# Supply.net
KiCad netlist of a schematic drawn in Altium Designer
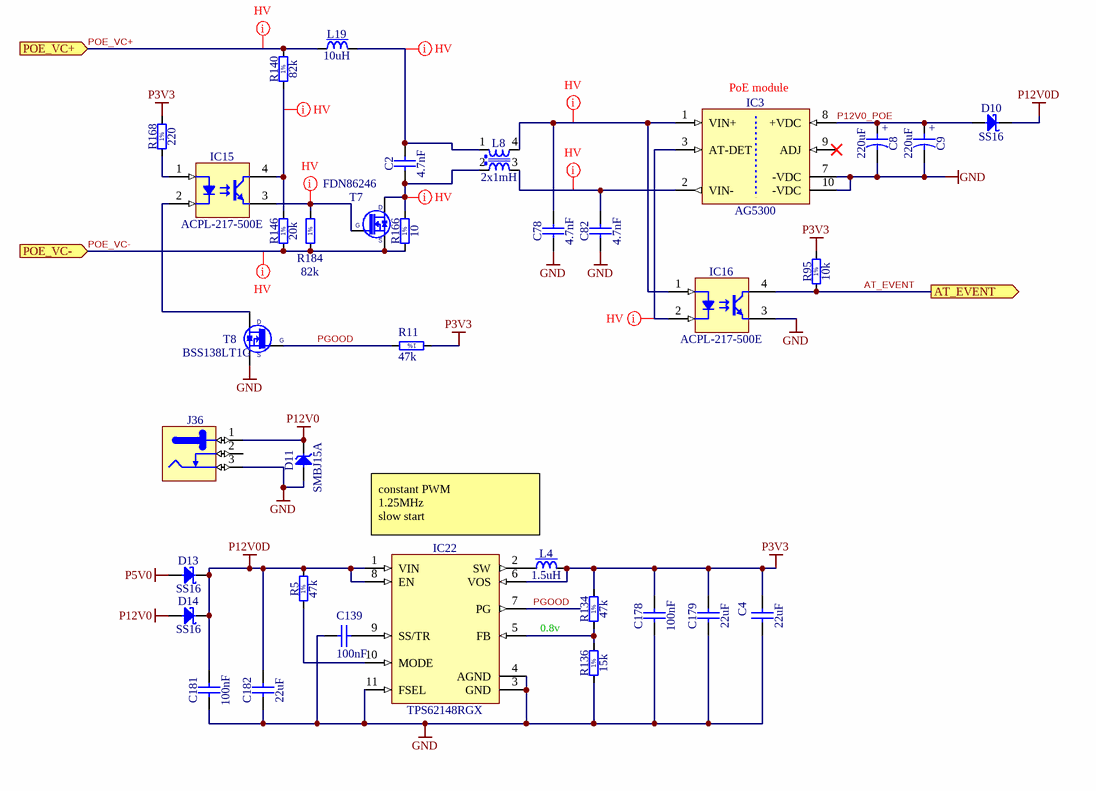
[diagram p0: Supply.SchDoc]

(export (version "E")
  (design (tool "Eeschema 10.0.6"))
  (components
    (comp (ref "C2")
      (value "4.7nF")
      (footprint "CAPC3216X140N")
      (description "Non-polarised capacitor")
      (fields
        (field (name "PART NUMBER") "CC1206_4.7NF_500V_10%_X7R")
        (field (name "VOLTAGE") "500V")
        (field (name "AUTHOR") "GK")
      )
      (libsource (lib "LIBRARY_SCH") (part "CAP_SMD_1206_4.7n_500V"))
    )
    (comp (ref "C4")
      (value "22uF")
      (footprint "CAPC2012X135N")
      (description "Non-polarised capacitor")
      (fields
        (field (name "PART NUMBER") "CC0805_22UF_16V_10%_X5R")
        (field (name "VOLTAGE") "16V")
        (field (name "AUTHOR") "CERN DEM JLC")
      )
      (libsource (lib "Capacitors") (part "Capacitor - non polarized"))
    )
    (comp (ref "C8")
      (value "220uF")
      (footprint "CAPMP7343X430N")
      (description "Polarised capacitor")
      (fields
        (field (name "PART NUMBER") "CTE7343-43_220UF_16V_10%")
        (field (name "VOLTAGE") "16V")
        (field (name "AUTHOR") "CERN DEM JLC")
      )
      (libsource (lib "Capacitors") (part "Capacitor - polarized"))
    )
    (comp (ref "C9")
      (value "220uF")
      (footprint "CAPMP7343X430N")
      (description "Polarised capacitor")
      (fields
        (field (name "PART NUMBER") "CTE7343-43_220UF_16V_10%")
        (field (name "VOLTAGE") "16V")
        (field (name "AUTHOR") "CERN DEM JLC")
      )
      (libsource (lib "Capacitors") (part "Capacitor - polarized"))
    )
    (comp (ref "C78")
      (value "4.7nF")
      (footprint "CAPC3216X140N")
      (description "Non-polarised capacitor")
      (fields
        (field (name "PART NUMBER") "CC1206_4.7NF_500V_10%_X7R")
        (field (name "VOLTAGE") "500V")
        (field (name "AUTHOR") "GK")
      )
      (libsource (lib "LIBRARY_SCH") (part "CAP_SMD_1206_4.7n_500V"))
    )
    (comp (ref "C82")
      (value "4.7nF")
      (footprint "CAPC3216X140N")
      (description "Non-polarised capacitor")
      (fields
        (field (name "PART NUMBER") "CC1206_4.7NF_500V_10%_X7R")
        (field (name "VOLTAGE") "500V")
        (field (name "AUTHOR") "GK")
      )
      (libsource (lib "LIBRARY_SCH") (part "CAP_SMD_1206_4.7n_500V"))
    )
    (comp (ref "C139")
      (value "100nF")
      (footprint "CAPC1005X55N")
      (description "Non-polarised capacitor")
      (fields
        (field (name "PART NUMBER") "CC0402_100NF_16V_10%_X5R")
        (field (name "VOLTAGE") "16V")
        (field (name "AUTHOR") "CERN DEM JLC")
      )
      (libsource (lib "Capacitors") (part "Capacitor - non polarized"))
    )
    (comp (ref "C178")
      (value "100nF")
      (footprint "CAPC1005X55N")
      (description "Non-polarised capacitor")
      (fields
        (field (name "PART NUMBER") "CC0402_100NF_16V_10%_X5R")
        (field (name "VOLTAGE") "16V")
        (field (name "AUTHOR") "CERN DEM JLC")
      )
      (libsource (lib "Capacitors") (part "Capacitor - non polarized"))
    )
    (comp (ref "C179")
      (value "22uF")
      (footprint "CAPC2012X135N")
      (description "Non-polarised capacitor")
      (fields
        (field (name "PART NUMBER") "CC0805_22UF_16V_10%_X5R")
        (field (name "VOLTAGE") "16V")
        (field (name "AUTHOR") "CERN DEM JLC")
      )
      (libsource (lib "Capacitors") (part "Capacitor - non polarized"))
    )
    (comp (ref "C181")
      (value "100nF")
      (footprint "CAPC1005X55N")
      (description "Non-polarised capacitor")
      (fields
        (field (name "PART NUMBER") "CC0402_100NF_16V_10%_X5R")
        (field (name "VOLTAGE") "16V")
        (field (name "AUTHOR") "CERN DEM JLC")
      )
      (libsource (lib "Capacitors") (part "Capacitor - non polarized"))
    )
    (comp (ref "C182")
      (value "22uF")
      (footprint "CAPC2012X135N")
      (description "Non-polarised capacitor")
      (fields
        (field (name "PART NUMBER") "CC0805_22UF_16V_10%_X5R")
        (field (name "VOLTAGE") "16V")
        (field (name "AUTHOR") "CERN DEM JLC")
      )
      (libsource (lib "Capacitors") (part "Capacitor - non polarized"))
    )
    (comp (ref "D10")
      (value "SS16")
      (footprint "DIOM5127X229N")
      (description "Schottky Diode")
      (fields
        (field (name "VOLTAGE") "60V")
        (field (name "POWER") "1A")
        (field (name "AUTHOR") "CERN DEM JLC")
      )
      (libsource (lib "ICs And Semiconductors") (part "Diode Schottky"))
    )
    (comp (ref "D11")
      (value "SMBJ15A")
      (footprint "DIOM5336X265N")
      (description "Zener Diode")
      (fields
        (field (name "VOLTAGE") "15V")
        (field (name "POWER") "600W")
        (field (name "AUTHOR") "CERN DEM JLC")
      )
      (libsource (lib "ICs And Semiconductors") (part "Diode Zener"))
    )
    (comp (ref "D13")
      (value "SS16")
      (footprint "DIOM5127X229N")
      (description "Schottky Diode")
      (fields
        (field (name "VOLTAGE") "60V")
        (field (name "POWER") "1A")
        (field (name "AUTHOR") "CERN DEM JLC")
      )
      (libsource (lib "ICs And Semiconductors") (part "Diode Schottky"))
    )
    (comp (ref "D14")
      (value "SS16")
      (footprint "DIOM5127X229N")
      (description "Schottky Diode")
      (fields
        (field (name "VOLTAGE") "60V")
        (field (name "POWER") "1A")
        (field (name "AUTHOR") "CERN DEM JLC")
      )
      (libsource (lib "ICs And Semiconductors") (part "Diode Schottky"))
    )
    (comp (ref "IC3")
      (value "AG5300")
      (footprint "SILVERTEL_AG5300")
      (description "Power-over-Ethernet Plus (POE+) Module")
      (fields (field (name "MANUFACTURER") "SILVERTEL") (field (name "AUTHOR") "CERN DEM JLC"))
      (libsource (lib "ICs And Semiconductors") (part "AG5300"))
    )
    (comp (ref "IC15")
      (value "ACPL-217-500E")
      (footprint "SOIC127P700X242-4N")
      (description "Single Optocoupler")
      (fields (field (name "MANUFACTURER") "AVAGO TECHNOLOGIES") (field (name "AUTHOR") "CERN DEM JLC"))
      (libsource (lib "ICs And Semiconductors") (part "Optocoupler Type7"))
    )
    (comp (ref "IC16")
      (value "ACPL-217-500E")
      (footprint "SOIC127P700X242-4N")
      (description "Single Optocoupler")
      (fields (field (name "MANUFACTURER") "AVAGO TECHNOLOGIES") (field (name "AUTHOR") "CERN DEM JLC"))
      (libsource (lib "ICs And Semiconductors") (part "Optocoupler Type7"))
    )
    (comp (ref "IC22")
      (value "TPS62148RGX")
      (footprint "TEXAS_RGX0011A")
      (description "3V-17V 2A Step-Down Converter, High Accuracy, With DCS-Control")
      (fields (field (name "MANUFACTURER") "TEXAS INSTRUMENTS") (field (name "AUTHOR") "CERN DEM MR"))
      (libsource (lib "ICs And Semiconductors") (part "TPS62148"))
    )
    (comp (ref "J36")
      (value "Jack")
      (footprint "CLIFF_FC68148(DC-10A)")
      (description "12V /  5A, 2.1mm Diameter Pin, DC Power Socket With  Switch. DC10A Type")
      (fields
        (field (name "PART NUMBER") "CLIFF_FC68148(DC-10A)")
        (field (name "MANUFACTURER") "CLIFF ELECTRONIC COMPONENTS")
        (field (name "AUTHOR") "CERN DEM JLC")
      )
      (libsource (lib "Connectors") (part "CLIFF_FC68148(DC-10A)"))
    )
    (comp (ref "L4")
      (value "1.5uH")
      (footprint "IND_TDK_SPM6530")
      (description "Inductor With Core")
      (fields
        (field (name "PART NUMBER") "IND_1.5UH_20%_TDK_SPM6530")
        (field (name "POWER") "11A")
        (field (name "AUTHOR") "CERN DEM MR")
      )
      (libsource (lib "Inductors & Transformers") (part "Inductor With Magnetic core"))
    )
    (comp (ref "L8")
      (value "2x1mH")
      (footprint "IND_WURTH_WE-SL2")
      (description "Inductor Common Mode")
      (fields
        (field (name "PART NUMBER") "IND_1MH_50%_WURTH_WE-SL2-744222")
        (field (name "POWER") "800mA")
        (field (name "AUTHOR") "CERN DEM JLC")
      )
      (libsource (lib "Inductors & Transformers") (part "Inductor Common Mode 1Dot-4 2Dot-3"))
    )
    (comp (ref "L19")
      (value "10uH")
      (footprint "IND_MURATA-PS_8400")
      (description "Inductor With Core")
      (fields
        (field (name "PART NUMBER") "IND_10UH_10%_MURATA-PS_8400")
        (field (name "POWER") "950mA")
        (field (name "AUTHOR") "CERN DEM JLC")
      )
      (libsource (lib "Inductors & Transformers") (part "Inductor With Magnetic core"))
    )
    (comp (ref "R5")
      (value "47k")
      (footprint "RESC1608X55N")
      (description "Resistor - 1%")
      (fields
        (field (name "PART NUMBER") "R0603_47K_1%_0.1W_100PPM")
        (field (name "POWER") "0.1W")
        (field (name "AUTHOR") "CERN DEM JLC")
      )
      (libsource (lib "Resistors") (part "Resistor - 1%"))
    )
    (comp (ref "R11")
      (value "47k")
      (footprint "RESC1608X55N")
      (description "Resistor - 1%")
      (fields
        (field (name "PART NUMBER") "R0603_47K_1%_0.1W_100PPM")
        (field (name "POWER") "0.1W")
        (field (name "AUTHOR") "CERN DEM JLC")
      )
      (libsource (lib "Resistors") (part "Resistor - 1%"))
    )
    (comp (ref "R95")
      (value "10k")
      (footprint "RESC1005X40N")
      (description "Resistor - 1%")
      (fields
        (field (name "PART NUMBER") "R0402_10K_1%_0.0625W_100PPM")
        (field (name "POWER") "0.0625W")
        (field (name "AUTHOR") "CERN DEM JLC")
      )
      (libsource (lib "Resistors") (part "Resistor - 1%"))
    )
    (comp (ref "R134")
      (value "47k")
      (footprint "RESC1608X55N")
      (description "Resistor - 1%")
      (fields
        (field (name "PART NUMBER") "R0603_47K_1%_0.1W_100PPM")
        (field (name "POWER") "0.1W")
        (field (name "AUTHOR") "CERN DEM JLC")
      )
      (libsource (lib "Resistors") (part "Resistor - 1%"))
    )
    (comp (ref "R136")
      (value "15k")
      (footprint "RESC1608X55N")
      (description "Resistor - 1%")
      (fields
        (field (name "PART NUMBER") "R0603_15K_1%_0.1W_100PPM")
        (field (name "POWER") "0.1W")
        (field (name "AUTHOR") "CERN DEM JMW")
      )
      (libsource (lib "Resistors") (part "Resistor - 1%"))
    )
    (comp (ref "R140")
      (value "82k")
      (footprint "RESC1608X55N")
      (description "Resistor - 1%")
      (fields
        (field (name "PART NUMBER") "R0603_82K_1%_0.1W_100PPM")
        (field (name "POWER") "0.1W")
        (field (name "AUTHOR") "CERN DEM JLC")
      )
      (libsource (lib "Resistors") (part "Resistor - 1%"))
    )
    (comp (ref "R146")
      (value "20k")
      (footprint "RESC1005X40N")
      (description "Resistor - 1%")
      (fields
        (field (name "PART NUMBER") "R0402_20K_1%_0.0625W_100PPM")
        (field (name "POWER") "0.0625W")
        (field (name "AUTHOR") "CERN DEM JLC")
      )
      (libsource (lib "Resistors") (part "Resistor - 1%"))
    )
    (comp (ref "R166")
      (value "10")
      (footprint "RESC2012X60N")
      (description "Resistor - 1%")
      (fields
        (field (name "PART NUMBER") "R0805_10R_1%_0.125W_200PPM")
        (field (name "POWER") "0.125W")
        (field (name "AUTHOR") "CERN DEM JLC")
      )
      (libsource (lib "Resistors") (part "Resistor - 1%"))
    )
    (comp (ref "R168")
      (value "220")
      (footprint "RESC1608X55N")
      (description "Resistor - 1%")
      (fields
        (field (name "PART NUMBER") "R0603_220R_1%_0.1W_100PPM")
        (field (name "POWER") "0.1W")
        (field (name "AUTHOR") "CERN DEM JLC")
      )
      (libsource (lib "Resistors") (part "Resistor - 1%"))
    )
    (comp (ref "R184")
      (value "82k")
      (footprint "RESC1608X55N")
      (description "Resistor - 1%")
      (fields
        (field (name "PART NUMBER") "R0603_82K_1%_0.1W_100PPM")
        (field (name "POWER") "0.1W")
        (field (name "AUTHOR") "CERN DEM JLC")
      )
      (libsource (lib "Resistors") (part "Resistor - 1%"))
    )
    (comp (ref "T7")
      (value "FDN86246")
      (footprint "SOT95P237X112-3N")
      (description "N-CHANNEL MOSFET WITH DIODE")
      (fields (field (name "MANUFACTURER") "ON SEMICONDUCTOR") (field (name "AUTHOR") "CERN DEM BC"))
      (libsource (lib "") (part "N-MOSFET-D 1G 2S 3D_1"))
    )
    (comp (ref "T8")
      (value "BSS138LT1G")
      (footprint "SOT95P240X110-3N")
      (description "N-CHANNEL MOSFET WITH DIODE")
      (fields (field (name "MANUFACTURER") "ON SEMICONDUCTOR") (field (name "AUTHOR") "CERN DEM JLC"))
      (libsource (lib "ICs And Semiconductors") (part "N-MOSFET-D 1G 2S 3D"))
    )
  )
  (nets
    (net (code "1") (name "/AT_EVENT") (class "Default")
      (node (ref "IC16") (pin "4") (pinfunction "C_4") (pintype "open_collector"))
      (node (ref "R95") (pin "1") (pinfunction "1_1") (pintype "passive"))
    )
    (net (code "2") (name "/P12V0_POE") (class "Default")
      (node (ref "C8") (pin "1") (pinfunction "1_1") (pintype "passive"))
      (node (ref "C9") (pin "1") (pinfunction "1_1") (pintype "passive"))
      (node (ref "D10") (pin "2") (pinfunction "A_2") (pintype "passive"))
      (node (ref "IC3") (pin "8") (pinfunction "+VDC_8") (pintype "input"))
    )
    (net (code "3") (name "/PGOOD") (class "Default")
      (node (ref "IC22") (pin "7") (pinfunction "PG_7") (pintype "output"))
      (node (ref "R11") (pin "2") (pinfunction "2_2") (pintype "passive"))
      (node (ref "T8") (pin "1") (pinfunction "G_1") (pintype "passive"))
    )
    (net (code "4") (name "/POE_VC+") (class "Default")
      (node (ref "L19") (pin "1") (pinfunction "1_1") (pintype "passive"))
      (node (ref "R140") (pin "2") (pinfunction "2_2") (pintype "passive"))
    )
    (net (code "5") (name "/POE_VC-") (class "Default")
      (node (ref "R146") (pin "1") (pinfunction "1_1") (pintype "passive"))
      (node (ref "R166") (pin "1") (pinfunction "1_1") (pintype "passive"))
      (node (ref "R184") (pin "1") (pinfunction "1_1") (pintype "passive"))
      (node (ref "T7") (pin "2") (pinfunction "S_2") (pintype "passive"))
    )
    (net (code "6") (name "GND") (class "Default")
      (node (ref "C139") (pin "2") (pinfunction "2_2") (pintype "passive"))
      (node (ref "C178") (pin "1") (pinfunction "1_1") (pintype "passive"))
      (node (ref "C179") (pin "1") (pinfunction "1_1") (pintype "passive"))
      (node (ref "C181") (pin "1") (pinfunction "1_1") (pintype "passive"))
      (node (ref "C182") (pin "1") (pinfunction "1_1") (pintype "passive"))
      (node (ref "C4") (pin "1") (pinfunction "1_1") (pintype "passive"))
      (node (ref "C78") (pin "1") (pinfunction "1_1") (pintype "passive"))
      (node (ref "C8") (pin "2") (pinfunction "2_2") (pintype "passive"))
      (node (ref "C82") (pin "1") (pinfunction "1_1") (pintype "passive"))
      (node (ref "C9") (pin "2") (pinfunction "2_2") (pintype "passive"))
      (node (ref "D11") (pin "2") (pinfunction "A_2") (pintype "passive"))
      (node (ref "IC16") (pin "3") (pinfunction "E_3") (pintype "open_emitter"))
      (node (ref "IC22") (pin "11") (pinfunction "FSEL_11") (pintype "input"))
      (node (ref "IC22") (pin "3") (pinfunction "GND_3") (pintype "power_in"))
      (node (ref "IC22") (pin "4") (pinfunction "AGND_4") (pintype "power_in"))
      (node (ref "IC3") (pin "10") (pinfunction "-VDC_10") (pintype "power_in"))
      (node (ref "IC3") (pin "7") (pinfunction "-VDC_7") (pintype "power_in"))
      (node (ref "J36") (pin "3") (pinfunction "3_3") (pintype "bidirectional"))
      (node (ref "R136") (pin "1") (pinfunction "1_1") (pintype "passive"))
      (node (ref "T8") (pin "2") (pinfunction "S_2") (pintype "passive"))
    )
    (net (code "7") (name "Net-(C2-Pad2)") (class "Default")
      (node (ref "C2") (pin "2") (pinfunction "2_2") (pintype "passive"))
      (node (ref "L19") (pin "2") (pinfunction "2_2") (pintype "passive"))
      (node (ref "L8") (pin "1") (pinfunction "1_1") (pintype "passive"))
    )
    (net (code "8") (name "Net-(IC3-AT-DET)") (class "Default")
      (node (ref "IC16") (pin "2") (pinfunction "C_2") (pintype "input"))
      (node (ref "IC3") (pin "3") (pinfunction "AT-DET_3") (pintype "input"))
    )
    (net (code "9") (name "Net-(IC3-VIN-)") (class "Default")
      (node (ref "C82") (pin "2") (pinfunction "2_2") (pintype "passive"))
      (node (ref "IC3") (pin "2") (pinfunction "VIN-_2") (pintype "output"))
      (node (ref "L8") (pin "3") (pinfunction "3_3") (pintype "passive"))
    )
    (net (code "10") (name "Net-(IC15-A)") (class "Default")
      (node (ref "IC15") (pin "1") (pinfunction "A_1") (pintype "input"))
      (node (ref "R168") (pin "1") (pinfunction "1_1") (pintype "passive"))
    )
    (net (code "11") (name "Net-(IC15-C-Pad4)") (class "Default")
      (node (ref "IC15") (pin "4") (pinfunction "C_4") (pintype "open_collector"))
      (node (ref "R140") (pin "1") (pinfunction "1_1") (pintype "passive"))
      (node (ref "R146") (pin "2") (pinfunction "2_2") (pintype "passive"))
    )
    (net (code "12") (name "Net-(IC15-E)") (class "Default")
      (node (ref "IC15") (pin "3") (pinfunction "E_3") (pintype "open_emitter"))
      (node (ref "R184") (pin "2") (pinfunction "2_2") (pintype "passive"))
      (node (ref "T7") (pin "1") (pinfunction "G_1") (pintype "passive"))
    )
    (net (code "13") (name "Net-(IC16-A)") (class "Default")
      (node (ref "C78") (pin "2") (pinfunction "2_2") (pintype "passive"))
      (node (ref "IC16") (pin "1") (pinfunction "A_1") (pintype "input"))
      (node (ref "IC3") (pin "1") (pinfunction "VIN+_1") (pintype "input"))
      (node (ref "L8") (pin "4") (pinfunction "4_4") (pintype "passive"))
    )
    (net (code "14") (name "Net-(IC22-FB)") (class "Default")
      (node (ref "IC22") (pin "5") (pinfunction "FB_5") (pintype "input"))
      (node (ref "R134") (pin "1") (pinfunction "1_1") (pintype "passive"))
      (node (ref "R136") (pin "2") (pinfunction "2_2") (pintype "passive"))
    )
    (net (code "15") (name "Net-(IC22-MODE)") (class "Default")
      (node (ref "IC22") (pin "10") (pinfunction "MODE_10") (pintype "input"))
      (node (ref "R5") (pin "1") (pinfunction "1_1") (pintype "passive"))
    )
    (net (code "16") (name "Net-(IC22-SS{slash}TR)") (class "Default")
      (node (ref "C139") (pin "1") (pinfunction "1_1") (pintype "passive"))
      (node (ref "IC22") (pin "9") (pinfunction "SS/TR_9") (pintype "input"))
    )
    (net (code "17") (name "Net-(IC22-SW)") (class "Default")
      (node (ref "IC22") (pin "2") (pinfunction "SW_2") (pintype "output"))
      (node (ref "L4") (pin "1") (pinfunction "1_1") (pintype "passive"))
    )
    (net (code "18") (name "Net-(T7-D)") (class "Default")
      (node (ref "C2") (pin "1") (pinfunction "1_1") (pintype "passive"))
      (node (ref "L8") (pin "2") (pinfunction "2_2") (pintype "passive"))
      (node (ref "R166") (pin "2") (pinfunction "2_2") (pintype "passive"))
      (node (ref "T7") (pin "3") (pinfunction "D_3") (pintype "passive"))
    )
    (net (code "19") (name "Net-(T8-D)") (class "Default")
      (node (ref "IC15") (pin "2") (pinfunction "C_2") (pintype "input"))
      (node (ref "T8") (pin "3") (pinfunction "D_3") (pintype "passive"))
    )
    (net (code "20") (name "P3V3") (class "Default")
      (node (ref "C178") (pin "2") (pinfunction "2_2") (pintype "passive"))
      (node (ref "C179") (pin "2") (pinfunction "2_2") (pintype "passive"))
      (node (ref "C4") (pin "2") (pinfunction "2_2") (pintype "passive"))
      (node (ref "IC22") (pin "6") (pinfunction "VOS_6") (pintype "input"))
      (node (ref "L4") (pin "2") (pinfunction "2_2") (pintype "passive"))
      (node (ref "R11") (pin "1") (pinfunction "1_1") (pintype "passive"))
      (node (ref "R134") (pin "2") (pinfunction "2_2") (pintype "passive"))
      (node (ref "R168") (pin "2") (pinfunction "2_2") (pintype "passive"))
      (node (ref "R95") (pin "2") (pinfunction "2_2") (pintype "passive"))
    )
    (net (code "21") (name "P5V0") (class "Default")
      (node (ref "D13") (pin "2") (pinfunction "A_2") (pintype "passive"))
    )
    (net (code "22") (name "P12V0") (class "Default")
      (node (ref "D11") (pin "1") (pinfunction "C_1") (pintype "passive"))
      (node (ref "D14") (pin "2") (pinfunction "A_2") (pintype "passive"))
      (node (ref "J36") (pin "1") (pinfunction "1_1") (pintype "bidirectional"))
    )
    (net (code "23") (name "P12V0D") (class "Default")
      (node (ref "C181") (pin "2") (pinfunction "2_2") (pintype "passive"))
      (node (ref "C182") (pin "2") (pinfunction "2_2") (pintype "passive"))
      (node (ref "D10") (pin "1") (pinfunction "C_1") (pintype "passive"))
      (node (ref "D13") (pin "1") (pinfunction "C_1") (pintype "passive"))
      (node (ref "D14") (pin "1") (pinfunction "C_1") (pintype "passive"))
      (node (ref "IC22") (pin "1") (pinfunction "VIN_1") (pintype "input"))
      (node (ref "IC22") (pin "8") (pinfunction "EN_8") (pintype "input"))
      (node (ref "R5") (pin "2") (pinfunction "2_2") (pintype "passive"))
    )
    (net (code "24") (name "unconnected-(IC3-ADJ-Pad9)") (class "Default")
      (node (ref "IC3") (pin "9") (pinfunction "ADJ_9") (pintype "input+no_connect"))
    )
    (net (code "25") (name "unconnected-(J36-Pad2)") (class "Default")
      (node (ref "J36") (pin "2") (pinfunction "2_2") (pintype "bidirectional"))
    )
  )
)
